# Sunflower_Schaltplan.net
KiCad netlist of a schematic drawn in EAGLE
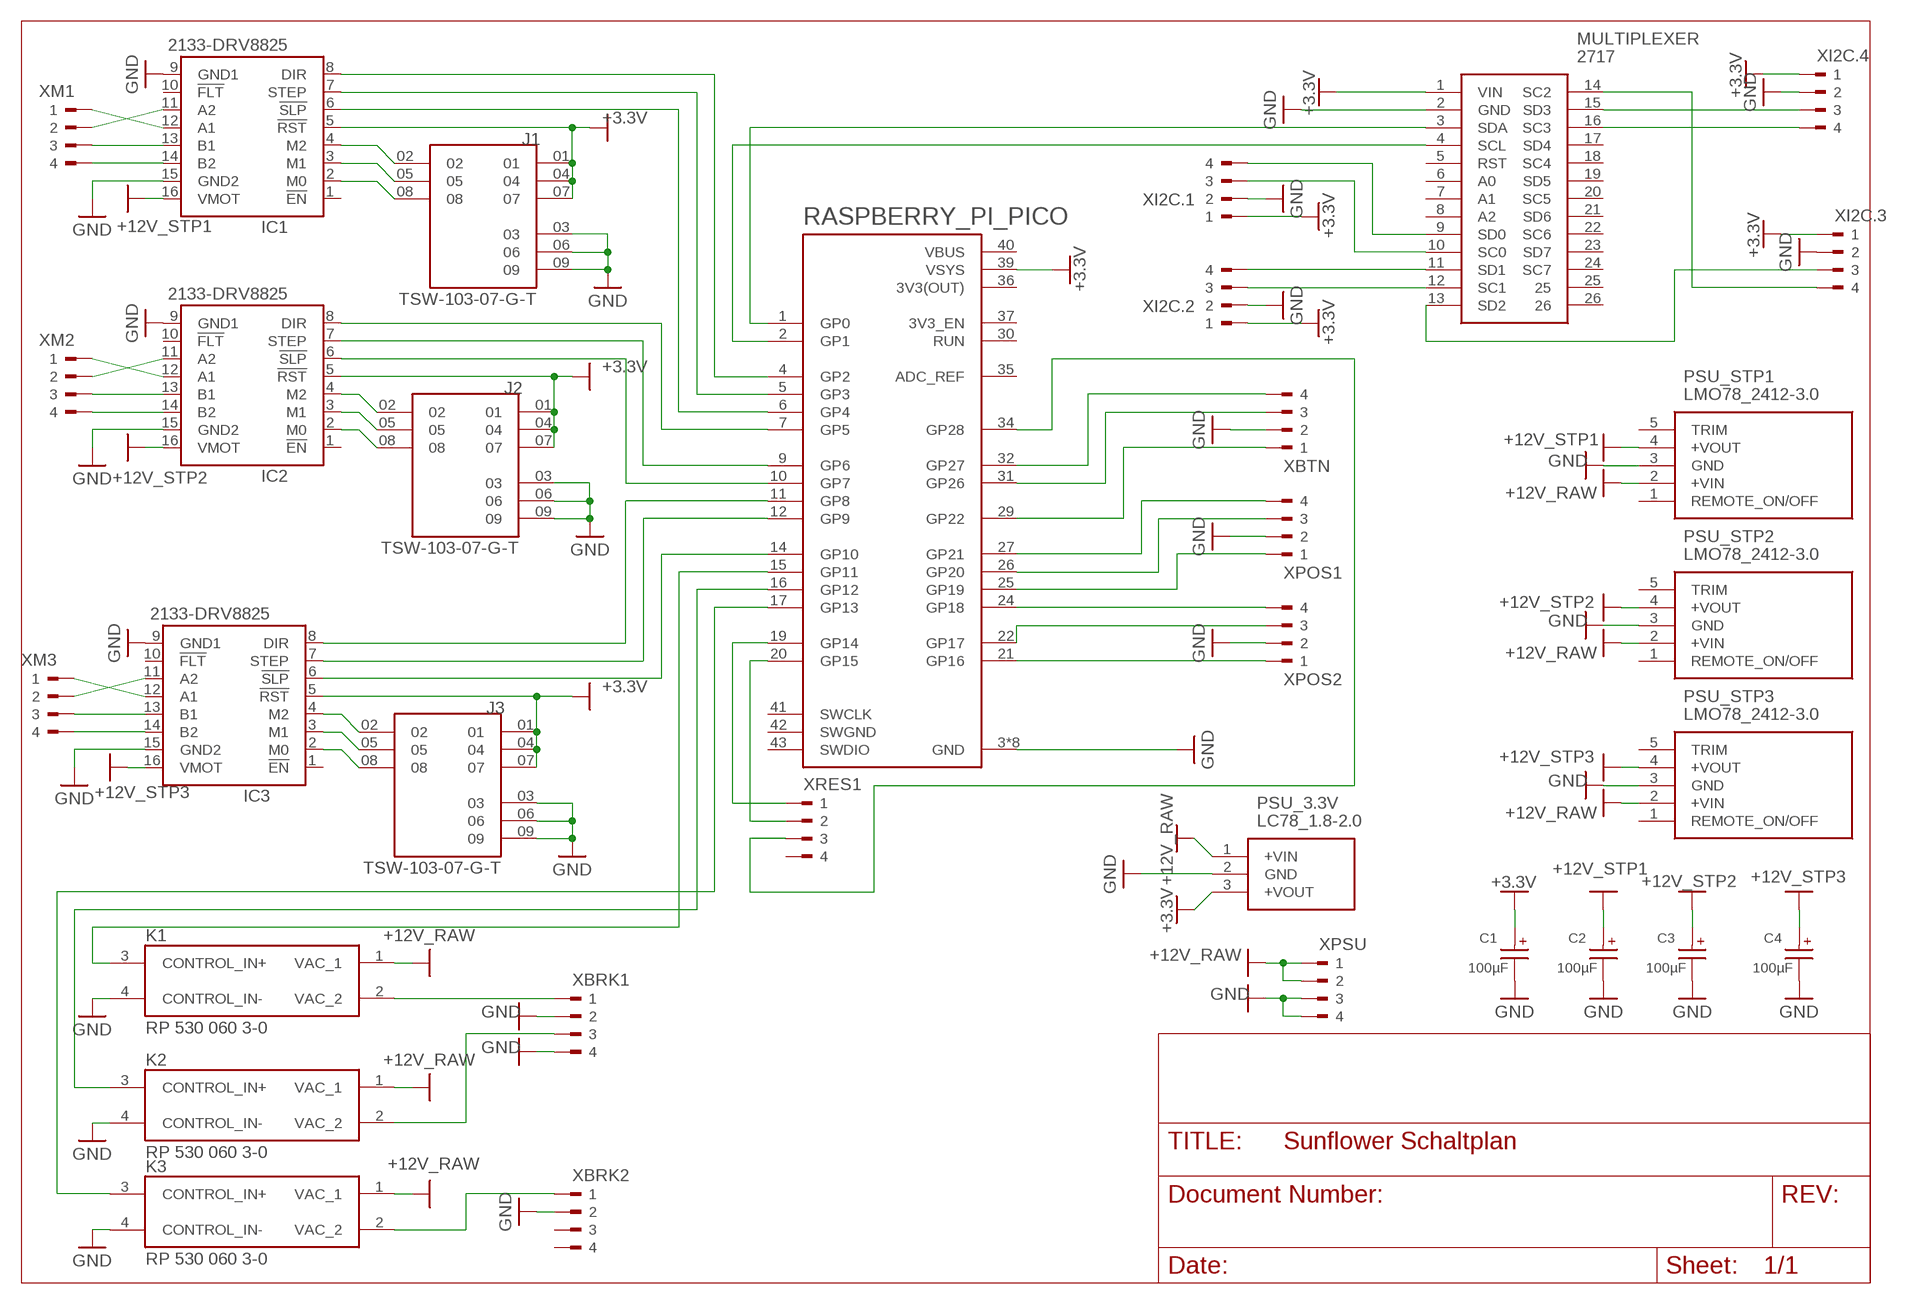
[diagram p0: schematic, sheet 1]

(export (version "E")
  (design (tool "Eeschema 10.0.6"))
  (components
    (comp (ref "C1")
      (value "100µF")
      (footprint "eagle-import:WCAP-ATET_10X16(DXL)")
      (libsource (lib "eagle-import") (part "WCAP-ATET_10X16_860130275006"))
    )
    (comp (ref "C2")
      (value "100µF")
      (footprint "eagle-import:WCAP-ATET_10X16(DXL)")
      (libsource (lib "eagle-import") (part "WCAP-ATET_10X16_860130275006"))
    )
    (comp (ref "C3")
      (value "100µF")
      (footprint "eagle-import:WCAP-ATET_10X16(DXL)")
      (libsource (lib "eagle-import") (part "WCAP-ATET_10X16_860130275006"))
    )
    (comp (ref "C4")
      (value "100µF")
      (footprint "eagle-import:WCAP-ATET_10X16(DXL)")
      (libsource (lib "eagle-import") (part "WCAP-ATET_10X16_860130275006"))
    )
    (comp (ref "IC1")
      (value "2133-DRV8825")
      (footprint "eagle-import:DRV8825")
      (libsource (lib "eagle-import") (part "2133-DRV8825"))
    )
    (comp (ref "IC2")
      (value "2133-DRV8825")
      (footprint "eagle-import:DRV8825")
      (libsource (lib "eagle-import") (part "2133-DRV8825"))
    )
    (comp (ref "IC3")
      (value "2133-DRV8825")
      (footprint "eagle-import:DRV8825")
      (libsource (lib "eagle-import") (part "2133-DRV8825"))
    )
    (comp (ref "J1")
      (value "TSW-103-07-G-T")
      (footprint "eagle-import:SAMTEC_TSW-103-07-G-T")
      (fields (field (name "MF") "Samtec Inc."))
      (libsource (lib "eagle-import") (part "TSW-103-07-G-T"))
    )
    (comp (ref "J2")
      (value "TSW-103-07-G-T")
      (footprint "eagle-import:SAMTEC_TSW-103-07-G-T")
      (fields (field (name "MF") "Samtec Inc."))
      (libsource (lib "eagle-import") (part "TSW-103-07-G-T"))
    )
    (comp (ref "J3")
      (value "TSW-103-07-G-T")
      (footprint "eagle-import:SAMTEC_TSW-103-07-G-T")
      (fields (field (name "MF") "Samtec Inc."))
      (libsource (lib "eagle-import") (part "TSW-103-07-G-T"))
    )
    (comp (ref "K1")
      (value "RP 530 060 3-0")
      (footprint "eagle-import:RELAY_RP1A23D5")
      (fields (field (name "MF") "Carlo Gavazzi Inc.") (field (name "MP") "RP1A23D5"))
      (libsource (lib "eagle-import") (part "RP1A23D5"))
    )
    (comp (ref "K2")
      (value "RP 530 060 3-0")
      (footprint "eagle-import:RELAY_RP1A23D5")
      (fields (field (name "MF") "Carlo Gavazzi Inc.") (field (name "MP") "RP1A23D5"))
      (libsource (lib "eagle-import") (part "RP1A23D5"))
    )
    (comp (ref "K3")
      (value "RP 530 060 3-0")
      (footprint "eagle-import:RELAY_RP1A23D5")
      (fields (field (name "MF") "Carlo Gavazzi Inc.") (field (name "MP") "RP1A23D5"))
      (libsource (lib "eagle-import") (part "RP1A23D5"))
    )
    (comp (ref "MULTIPLEXER")
      (value "2717")
      (footprint "eagle-import:2717")
      (fields (field (name "MOUSER_PART_NUMBER") "485-2717"))
      (libsource (lib "eagle-import") (part "2717"))
    )
    (comp (ref "PSU_3.3V")
      (value "LC78_1.8-2.0")
      (footprint "eagle-import:LC78_1820")
      (fields (field (name "MANUFACTURER_PART_NUMBER") "LC78_03-2.0"))
      (libsource (lib "eagle-import") (part "LC78_1.8-2.0"))
    )
    (comp (ref "PSU_STP1")
      (value "LMO78_2412-3.0")
      (footprint "eagle-import:LMO78_241230")
      (libsource (lib "eagle-import") (part "LMO78_2412-3.0"))
    )
    (comp (ref "PSU_STP2")
      (value "LMO78_2412-3.0")
      (footprint "eagle-import:LMO78_241230")
      (libsource (lib "eagle-import") (part "LMO78_2412-3.0"))
    )
    (comp (ref "PSU_STP3")
      (value "LMO78_2412-3.0")
      (footprint "eagle-import:LMO78_241230")
      (libsource (lib "eagle-import") (part "LMO78_2412-3.0"))
    )
    (comp (ref "RASPBERRY_PI_PICO")
      (value "RASPBERRY_PICOTH")
      (footprint "eagle-import:PICO-PKG-TH")
      (libsource (lib "eagle-import") (part "RASPBERRY_PICOTH"))
    )
    (comp (ref "XBRK1")
      (value "ANLOX_PT09304HBBN")
      (footprint "eagle-import:ANLOX_PT09304HBBN")
      (libsource (lib "eagle-import") (part "ANLOX_PT09304HBBN"))
    )
    (comp (ref "XBRK2")
      (value "ANLOX_PT09304HBBN")
      (footprint "eagle-import:ANLOX_PT09304HBBN")
      (libsource (lib "eagle-import") (part "ANLOX_PT09304HBBN"))
    )
    (comp (ref "XBTN")
      (value "ANLOX_PT09304HBBN")
      (footprint "eagle-import:ANLOX_PT09304HBBN")
      (libsource (lib "eagle-import") (part "ANLOX_PT09304HBBN"))
    )
    (comp (ref "XI2C.1")
      (value "ANLOX_PT09304HBBN")
      (footprint "eagle-import:ANLOX_PT09304HBBN")
      (libsource (lib "eagle-import") (part "ANLOX_PT09304HBBN"))
    )
    (comp (ref "XI2C.2")
      (value "ANLOX_PT09304HBBN")
      (footprint "eagle-import:ANLOX_PT09304HBBN")
      (libsource (lib "eagle-import") (part "ANLOX_PT09304HBBN"))
    )
    (comp (ref "XI2C.3")
      (value "ANLOX_PT09304HBBN")
      (footprint "eagle-import:ANLOX_PT09304HBBN")
      (libsource (lib "eagle-import") (part "ANLOX_PT09304HBBN"))
    )
    (comp (ref "XI2C.4")
      (value "ANLOX_PT09304HBBN")
      (footprint "eagle-import:ANLOX_PT09304HBBN")
      (libsource (lib "eagle-import") (part "ANLOX_PT09304HBBN"))
    )
    (comp (ref "XM1")
      (value "ANLOX_PT09304HBBN")
      (footprint "eagle-import:ANLOX_PT09304HBBN")
      (libsource (lib "eagle-import") (part "ANLOX_PT09304HBBN"))
    )
    (comp (ref "XM2")
      (value "ANLOX_PT09304HBBN")
      (footprint "eagle-import:ANLOX_PT09304HBBN")
      (libsource (lib "eagle-import") (part "ANLOX_PT09304HBBN"))
    )
    (comp (ref "XM3")
      (value "ANLOX_PT09304HBBN")
      (footprint "eagle-import:ANLOX_PT09304HBBN")
      (libsource (lib "eagle-import") (part "ANLOX_PT09304HBBN"))
    )
    (comp (ref "XPOS1")
      (value "ANLOX_PT09304HBBN")
      (footprint "eagle-import:ANLOX_PT09304HBBN")
      (libsource (lib "eagle-import") (part "ANLOX_PT09304HBBN"))
    )
    (comp (ref "XPOS2")
      (value "ANLOX_PT09304HBBN")
      (footprint "eagle-import:ANLOX_PT09304HBBN")
      (libsource (lib "eagle-import") (part "ANLOX_PT09304HBBN"))
    )
    (comp (ref "XPSU")
      (value "ANLOX_PT09304HBBN")
      (footprint "eagle-import:ANLOX_PT09304HBBN")
      (libsource (lib "eagle-import") (part "ANLOX_PT09304HBBN"))
    )
    (comp (ref "XRES1")
      (value "ANLOX_PT09304HBBN")
      (footprint "eagle-import:ANLOX_PT09304HBBN")
      (libsource (lib "eagle-import") (part "ANLOX_PT09304HBBN"))
    )
  )
  (nets
    (net (code "1") (name "+3.3V") (class "Default")
      (node (ref "C1") (pin "1") (pinfunction "+_1") (pintype "passive"))
      (node (ref "IC1") (pin "5") (pinfunction "~{RST}_5") (pintype "input"))
      (node (ref "IC2") (pin "5") (pinfunction "~{RST}_5") (pintype "input"))
      (node (ref "IC3") (pin "5") (pinfunction "~{RST}_5") (pintype "input"))
      (node (ref "J1") (pin "01") (pinfunction "01_01") (pintype "passive"))
      (node (ref "J1") (pin "04") (pinfunction "04_04") (pintype "passive"))
      (node (ref "J1") (pin "07") (pinfunction "07_07") (pintype "passive"))
      (node (ref "J2") (pin "01") (pinfunction "01_01") (pintype "passive"))
      (node (ref "J2") (pin "04") (pinfunction "04_04") (pintype "passive"))
      (node (ref "J2") (pin "07") (pinfunction "07_07") (pintype "passive"))
      (node (ref "J3") (pin "01") (pinfunction "01_01") (pintype "passive"))
      (node (ref "J3") (pin "04") (pinfunction "04_04") (pintype "passive"))
      (node (ref "J3") (pin "07") (pinfunction "07_07") (pintype "passive"))
      (node (ref "MULTIPLEXER") (pin "1") (pinfunction "VIN_1") (pintype "bidirectional"))
      (node (ref "PSU_3.3V") (pin "3") (pinfunction "+VOUT_3") (pintype "bidirectional"))
      (node (ref "RASPBERRY_PI_PICO") (pin "39") (pinfunction "VSYS_39") (pintype "power_in"))
      (node (ref "XI2C.1") (pin "1") (pinfunction "1_1") (pintype "passive"))
      (node (ref "XI2C.2") (pin "1") (pinfunction "1_1") (pintype "passive"))
      (node (ref "XI2C.3") (pin "1") (pinfunction "1_1") (pintype "passive"))
      (node (ref "XI2C.4") (pin "1") (pinfunction "1_1") (pintype "passive"))
    )
    (net (code "2") (name "+12V_RAW") (class "Default")
      (node (ref "K1") (pin "1") (pinfunction "VAC_1_1") (pintype "output"))
      (node (ref "K2") (pin "1") (pinfunction "VAC_1_1") (pintype "output"))
      (node (ref "K3") (pin "1") (pinfunction "VAC_1_1") (pintype "output"))
      (node (ref "PSU_3.3V") (pin "1") (pinfunction "+VIN_1") (pintype "bidirectional"))
      (node (ref "PSU_STP1") (pin "2") (pinfunction "+VIN_2") (pintype "bidirectional"))
      (node (ref "PSU_STP2") (pin "2") (pinfunction "+VIN_2") (pintype "bidirectional"))
      (node (ref "PSU_STP3") (pin "2") (pinfunction "+VIN_2") (pintype "bidirectional"))
      (node (ref "XPSU") (pin "1") (pinfunction "1_1") (pintype "passive"))
      (node (ref "XPSU") (pin "2") (pinfunction "2_2") (pintype "passive"))
    )
    (net (code "3") (name "+12V_STP1") (class "Default")
      (node (ref "C2") (pin "1") (pinfunction "+_1") (pintype "passive"))
      (node (ref "IC1") (pin "16") (pinfunction "VMOT_16") (pintype "power_in"))
      (node (ref "PSU_STP1") (pin "4") (pinfunction "+VOUT_4") (pintype "bidirectional"))
    )
    (net (code "4") (name "+12V_STP2") (class "Default")
      (node (ref "C3") (pin "1") (pinfunction "+_1") (pintype "passive"))
      (node (ref "IC2") (pin "16") (pinfunction "VMOT_16") (pintype "power_in"))
      (node (ref "PSU_STP2") (pin "4") (pinfunction "+VOUT_4") (pintype "bidirectional"))
    )
    (net (code "5") (name "+12V_STP3") (class "Default")
      (node (ref "C4") (pin "1") (pinfunction "+_1") (pintype "passive"))
      (node (ref "IC3") (pin "16") (pinfunction "VMOT_16") (pintype "power_in"))
      (node (ref "PSU_STP3") (pin "4") (pinfunction "+VOUT_4") (pintype "bidirectional"))
    )
    (net (code "6") (name "/3V3(OUT)") (class "Default")
      (node (ref "RASPBERRY_PI_PICO") (pin "36") (pinfunction "3V3(OUT)_36") (pintype "power_in"))
    )
    (net (code "7") (name "/SWGND") (class "Default")
      (node (ref "RASPBERRY_PI_PICO") (pin "42") (pinfunction "SWGND_42") (pintype "power_in"))
    )
    (net (code "8") (name "/VBUS") (class "Default")
      (node (ref "RASPBERRY_PI_PICO") (pin "40") (pinfunction "VBUS_40") (pintype "power_in"))
    )
    (net (code "9") (name "GND") (class "Default")
      (node (ref "C1") (pin "2") (pinfunction "-_2") (pintype "passive"))
      (node (ref "C2") (pin "2") (pinfunction "-_2") (pintype "passive"))
      (node (ref "C3") (pin "2") (pinfunction "-_2") (pintype "passive"))
      (node (ref "C4") (pin "2") (pinfunction "-_2") (pintype "passive"))
      (node (ref "IC1") (pin "15") (pinfunction "GND2_15") (pintype "power_in"))
      (node (ref "IC1") (pin "9") (pinfunction "GND1_9") (pintype "power_in"))
      (node (ref "IC2") (pin "15") (pinfunction "GND2_15") (pintype "power_in"))
      (node (ref "IC2") (pin "9") (pinfunction "GND1_9") (pintype "power_in"))
      (node (ref "IC3") (pin "15") (pinfunction "GND2_15") (pintype "power_in"))
      (node (ref "IC3") (pin "9") (pinfunction "GND1_9") (pintype "power_in"))
      (node (ref "J1") (pin "03") (pinfunction "03_03") (pintype "passive"))
      (node (ref "J1") (pin "06") (pinfunction "06_06") (pintype "passive"))
      (node (ref "J1") (pin "09") (pinfunction "09_09") (pintype "passive"))
      (node (ref "J2") (pin "03") (pinfunction "03_03") (pintype "passive"))
      (node (ref "J2") (pin "06") (pinfunction "06_06") (pintype "passive"))
      (node (ref "J2") (pin "09") (pinfunction "09_09") (pintype "passive"))
      (node (ref "J3") (pin "03") (pinfunction "03_03") (pintype "passive"))
      (node (ref "J3") (pin "06") (pinfunction "06_06") (pintype "passive"))
      (node (ref "J3") (pin "09") (pinfunction "09_09") (pintype "passive"))
      (node (ref "K1") (pin "4") (pinfunction "CONTROL_IN-_4") (pintype "input"))
      (node (ref "K2") (pin "4") (pinfunction "CONTROL_IN-_4") (pintype "input"))
      (node (ref "K3") (pin "4") (pinfunction "CONTROL_IN-_4") (pintype "input"))
      (node (ref "MULTIPLEXER") (pin "2") (pinfunction "GND_2") (pintype "bidirectional"))
      (node (ref "PSU_3.3V") (pin "2") (pinfunction "GND_2") (pintype "bidirectional"))
      (node (ref "PSU_STP1") (pin "3") (pinfunction "GND_3") (pintype "bidirectional"))
      (node (ref "PSU_STP2") (pin "3") (pinfunction "GND_3") (pintype "bidirectional"))
      (node (ref "PSU_STP3") (pin "3") (pinfunction "GND_3") (pintype "bidirectional"))
      (node (ref "RASPBERRY_PI_PICO") (pin "13") (pinfunction "GND_13") (pintype "power_in"))
      (node (ref "RASPBERRY_PI_PICO") (pin "18") (pinfunction "GND_18") (pintype "power_in"))
      (node (ref "RASPBERRY_PI_PICO") (pin "23") (pinfunction "GND_23") (pintype "power_in"))
      (node (ref "RASPBERRY_PI_PICO") (pin "28") (pinfunction "GND_28") (pintype "power_in"))
      (node (ref "RASPBERRY_PI_PICO") (pin "3") (pinfunction "GND_3") (pintype "power_in"))
      (node (ref "RASPBERRY_PI_PICO") (pin "33") (pinfunction "GND_33") (pintype "power_in"))
      (node (ref "RASPBERRY_PI_PICO") (pin "38") (pinfunction "GND_38") (pintype "power_in"))
      (node (ref "RASPBERRY_PI_PICO") (pin "8") (pinfunction "GND_8") (pintype "power_in"))
      (node (ref "XBRK1") (pin "2") (pinfunction "2_2") (pintype "passive"))
      (node (ref "XBRK1") (pin "4") (pinfunction "4_4") (pintype "passive"))
      (node (ref "XBRK2") (pin "2") (pinfunction "2_2") (pintype "passive"))
      (node (ref "XBTN") (pin "2") (pinfunction "2_2") (pintype "passive"))
      (node (ref "XI2C.1") (pin "2") (pinfunction "2_2") (pintype "passive"))
      (node (ref "XI2C.2") (pin "2") (pinfunction "2_2") (pintype "passive"))
      (node (ref "XI2C.3") (pin "2") (pinfunction "2_2") (pintype "passive"))
      (node (ref "XI2C.4") (pin "2") (pinfunction "2_2") (pintype "passive"))
      (node (ref "XPOS1") (pin "2") (pinfunction "2_2") (pintype "passive"))
      (node (ref "XPOS2") (pin "2") (pinfunction "2_2") (pintype "passive"))
      (node (ref "XPSU") (pin "3") (pinfunction "3_3") (pintype "passive"))
      (node (ref "XPSU") (pin "4") (pinfunction "4_4") (pintype "passive"))
    )
    (net (code "10") (name "Net-(IC1-A1)") (class "Default")
      (node (ref "IC1") (pin "12") (pinfunction "A1_12") (pintype "output"))
      (node (ref "XM1") (pin "1") (pinfunction "1_1") (pintype "passive"))
    )
    (net (code "11") (name "Net-(IC1-A2)") (class "Default")
      (node (ref "IC1") (pin "11") (pinfunction "A2_11") (pintype "output"))
      (node (ref "XM1") (pin "2") (pinfunction "2_2") (pintype "passive"))
    )
    (net (code "12") (name "Net-(IC1-B1)") (class "Default")
      (node (ref "IC1") (pin "13") (pinfunction "B1_13") (pintype "output"))
      (node (ref "XM1") (pin "3") (pinfunction "3_3") (pintype "passive"))
    )
    (net (code "13") (name "Net-(IC1-B2)") (class "Default")
      (node (ref "IC1") (pin "14") (pinfunction "B2_14") (pintype "output"))
      (node (ref "XM1") (pin "4") (pinfunction "4_4") (pintype "passive"))
    )
    (net (code "14") (name "Net-(IC1-DIR)") (class "Default")
      (node (ref "IC1") (pin "8") (pinfunction "DIR_8") (pintype "input"))
      (node (ref "RASPBERRY_PI_PICO") (pin "4") (pinfunction "GP2_4") (pintype "bidirectional"))
    )
    (net (code "15") (name "Net-(IC1-M0)") (class "Default")
      (node (ref "IC1") (pin "2") (pinfunction "M0_2") (pintype "passive"))
      (node (ref "J1") (pin "08") (pinfunction "08_08") (pintype "passive"))
    )
    (net (code "16") (name "Net-(IC1-M1)") (class "Default")
      (node (ref "IC1") (pin "3") (pinfunction "M1_3") (pintype "passive"))
      (node (ref "J1") (pin "05") (pinfunction "05_05") (pintype "passive"))
    )
    (net (code "17") (name "Net-(IC1-M2)") (class "Default")
      (node (ref "IC1") (pin "4") (pinfunction "M2_4") (pintype "passive"))
      (node (ref "J1") (pin "02") (pinfunction "02_02") (pintype "passive"))
    )
    (net (code "18") (name "Net-(IC1-STEP)") (class "Default")
      (node (ref "IC1") (pin "7") (pinfunction "STEP_7") (pintype "input"))
      (node (ref "RASPBERRY_PI_PICO") (pin "5") (pinfunction "GP3_5") (pintype "bidirectional"))
    )
    (net (code "19") (name "Net-(IC1-~{SLP})") (class "Default")
      (node (ref "IC1") (pin "6") (pinfunction "~{SLP}_6") (pintype "input"))
      (node (ref "RASPBERRY_PI_PICO") (pin "6") (pinfunction "GP4_6") (pintype "bidirectional"))
    )
    (net (code "20") (name "Net-(IC2-A1)") (class "Default")
      (node (ref "IC2") (pin "12") (pinfunction "A1_12") (pintype "output"))
      (node (ref "XM2") (pin "1") (pinfunction "1_1") (pintype "passive"))
    )
    (net (code "21") (name "Net-(IC2-A2)") (class "Default")
      (node (ref "IC2") (pin "11") (pinfunction "A2_11") (pintype "output"))
      (node (ref "XM2") (pin "2") (pinfunction "2_2") (pintype "passive"))
    )
    (net (code "22") (name "Net-(IC2-B1)") (class "Default")
      (node (ref "IC2") (pin "13") (pinfunction "B1_13") (pintype "output"))
      (node (ref "XM2") (pin "3") (pinfunction "3_3") (pintype "passive"))
    )
    (net (code "23") (name "Net-(IC2-B2)") (class "Default")
      (node (ref "IC2") (pin "14") (pinfunction "B2_14") (pintype "output"))
      (node (ref "XM2") (pin "4") (pinfunction "4_4") (pintype "passive"))
    )
    (net (code "24") (name "Net-(IC2-DIR)") (class "Default")
      (node (ref "IC2") (pin "8") (pinfunction "DIR_8") (pintype "input"))
      (node (ref "RASPBERRY_PI_PICO") (pin "7") (pinfunction "GP5_7") (pintype "bidirectional"))
    )
    (net (code "25") (name "Net-(IC2-M0)") (class "Default")
      (node (ref "IC2") (pin "2") (pinfunction "M0_2") (pintype "passive"))
      (node (ref "J2") (pin "08") (pinfunction "08_08") (pintype "passive"))
    )
    (net (code "26") (name "Net-(IC2-M1)") (class "Default")
      (node (ref "IC2") (pin "3") (pinfunction "M1_3") (pintype "passive"))
      (node (ref "J2") (pin "05") (pinfunction "05_05") (pintype "passive"))
    )
    (net (code "27") (name "Net-(IC2-M2)") (class "Default")
      (node (ref "IC2") (pin "4") (pinfunction "M2_4") (pintype "passive"))
      (node (ref "J2") (pin "02") (pinfunction "02_02") (pintype "passive"))
    )
    (net (code "28") (name "Net-(IC2-STEP)") (class "Default")
      (node (ref "IC2") (pin "7") (pinfunction "STEP_7") (pintype "input"))
      (node (ref "RASPBERRY_PI_PICO") (pin "9") (pinfunction "GP6_9") (pintype "bidirectional"))
    )
    (net (code "29") (name "Net-(IC2-~{SLP})") (class "Default")
      (node (ref "IC2") (pin "6") (pinfunction "~{SLP}_6") (pintype "input"))
      (node (ref "RASPBERRY_PI_PICO") (pin "10") (pinfunction "GP7_10") (pintype "bidirectional"))
    )
    (net (code "30") (name "Net-(IC3-A1)") (class "Default")
      (node (ref "IC3") (pin "12") (pinfunction "A1_12") (pintype "output"))
      (node (ref "XM3") (pin "1") (pinfunction "1_1") (pintype "passive"))
    )
    (net (code "31") (name "Net-(IC3-A2)") (class "Default")
      (node (ref "IC3") (pin "11") (pinfunction "A2_11") (pintype "output"))
      (node (ref "XM3") (pin "2") (pinfunction "2_2") (pintype "passive"))
    )
    (net (code "32") (name "Net-(IC3-B1)") (class "Default")
      (node (ref "IC3") (pin "13") (pinfunction "B1_13") (pintype "output"))
      (node (ref "XM3") (pin "3") (pinfunction "3_3") (pintype "passive"))
    )
    (net (code "33") (name "Net-(IC3-B2)") (class "Default")
      (node (ref "IC3") (pin "14") (pinfunction "B2_14") (pintype "output"))
      (node (ref "XM3") (pin "4") (pinfunction "4_4") (pintype "passive"))
    )
    (net (code "34") (name "Net-(IC3-DIR)") (class "Default")
      (node (ref "IC3") (pin "8") (pinfunction "DIR_8") (pintype "input"))
      (node (ref "RASPBERRY_PI_PICO") (pin "11") (pinfunction "GP8_11") (pintype "bidirectional"))
    )
    (net (code "35") (name "Net-(IC3-M0)") (class "Default")
      (node (ref "IC3") (pin "2") (pinfunction "M0_2") (pintype "passive"))
      (node (ref "J3") (pin "08") (pinfunction "08_08") (pintype "passive"))
    )
    (net (code "36") (name "Net-(IC3-M1)") (class "Default")
      (node (ref "IC3") (pin "3") (pinfunction "M1_3") (pintype "passive"))
      (node (ref "J3") (pin "05") (pinfunction "05_05") (pintype "passive"))
    )
    (net (code "37") (name "Net-(IC3-M2)") (class "Default")
      (node (ref "IC3") (pin "4") (pinfunction "M2_4") (pintype "passive"))
      (node (ref "J3") (pin "02") (pinfunction "02_02") (pintype "passive"))
    )
    (net (code "38") (name "Net-(IC3-STEP)") (class "Default")
      (node (ref "IC3") (pin "7") (pinfunction "STEP_7") (pintype "input"))
      (node (ref "RASPBERRY_PI_PICO") (pin "12") (pinfunction "GP9_12") (pintype "bidirectional"))
    )
    (net (code "39") (name "Net-(IC3-~{SLP})") (class "Default")
      (node (ref "IC3") (pin "6") (pinfunction "~{SLP}_6") (pintype "input"))
      (node (ref "RASPBERRY_PI_PICO") (pin "14") (pinfunction "GP10_14") (pintype "bidirectional"))
    )
    (net (code "40") (name "Net-(K1-CONTROL_IN+)") (class "Default")
      (node (ref "K1") (pin "3") (pinfunction "CONTROL_IN+_3") (pintype "input"))
      (node (ref "RASPBERRY_PI_PICO") (pin "15") (pinfunction "GP11_15") (pintype "bidirectional"))
    )
    (net (code "41") (name "Net-(K1-VAC_2)") (class "Default")
      (node (ref "K1") (pin "2") (pinfunction "VAC_2_2") (pintype "output"))
      (node (ref "XBRK1") (pin "1") (pinfunction "1_1") (pintype "passive"))
    )
    (net (code "42") (name "Net-(K2-CONTROL_IN+)") (class "Default")
      (node (ref "K2") (pin "3") (pinfunction "CONTROL_IN+_3") (pintype "input"))
      (node (ref "RASPBERRY_PI_PICO") (pin "16") (pinfunction "GP12_16") (pintype "bidirectional"))
    )
    (net (code "43") (name "Net-(K2-VAC_2)") (class "Default")
      (node (ref "K2") (pin "2") (pinfunction "VAC_2_2") (pintype "output"))
      (node (ref "XBRK1") (pin "3") (pinfunction "3_3") (pintype "passive"))
    )
    (net (code "44") (name "Net-(K3-CONTROL_IN+)") (class "Default")
      (node (ref "K3") (pin "3") (pinfunction "CONTROL_IN+_3") (pintype "input"))
      (node (ref "RASPBERRY_PI_PICO") (pin "17") (pinfunction "GP13_17") (pintype "bidirectional"))
    )
    (net (code "45") (name "Net-(K3-VAC_2)") (class "Default")
      (node (ref "K3") (pin "2") (pinfunction "VAC_2_2") (pintype "output"))
      (node (ref "XBRK2") (pin "1") (pinfunction "1_1") (pintype "passive"))
    )
    (net (code "46") (name "Net-(MULTIPLEXER-SC0)") (class "Default")
      (node (ref "MULTIPLEXER") (pin "10") (pinfunction "SC0_10") (pintype "bidirectional"))
      (node (ref "XI2C.1") (pin "3") (pinfunction "3_3") (pintype "passive"))
    )
    (net (code "47") (name "Net-(MULTIPLEXER-SC1)") (class "Default")
      (node (ref "MULTIPLEXER") (pin "12") (pinfunction "SC1_12") (pintype "bidirectional"))
      (node (ref "XI2C.2") (pin "3") (pinfunction "3_3") (pintype "passive"))
    )
    (net (code "48") (name "Net-(MULTIPLEXER-SC2)") (class "Default")
      (node (ref "MULTIPLEXER") (pin "14") (pinfunction "SC2_14") (pintype "bidirectional"))
      (node (ref "XI2C.3") (pin "4") (pinfunction "4_4") (pintype "passive"))
    )
    (net (code "49") (name "Net-(MULTIPLEXER-SC3)") (class "Default")
      (node (ref "MULTIPLEXER") (pin "16") (pinfunction "SC3_16") (pintype "bidirectional"))
      (node (ref "XI2C.4") (pin "4") (pinfunction "4_4") (pintype "passive"))
    )
    (net (code "50") (name "Net-(MULTIPLEXER-SCL)") (class "Default")
      (node (ref "MULTIPLEXER") (pin "4") (pinfunction "SCL_4") (pintype "bidirectional"))
      (node (ref "RASPBERRY_PI_PICO") (pin "2") (pinfunction "GP1_2") (pintype "bidirectional"))
    )
    (net (code "51") (name "Net-(MULTIPLEXER-SD0)") (class "Default")
      (node (ref "MULTIPLEXER") (pin "9") (pinfunction "SD0_9") (pintype "bidirectional"))
      (node (ref "XI2C.1") (pin "4") (pinfunction "4_4") (pintype "passive"))
    )
    (net (code "52") (name "Net-(MULTIPLEXER-SD1)") (class "Default")
      (node (ref "MULTIPLEXER") (pin "11") (pinfunction "SD1_11") (pintype "bidirectional"))
      (node (ref "XI2C.2") (pin "4") (pinfunction "4_4") (pintype "passive"))
    )
    (net (code "53") (name "Net-(MULTIPLEXER-SD2)") (class "Default")
      (node (ref "MULTIPLEXER") (pin "13") (pinfunction "SD2_13") (pintype "bidirectional"))
      (node (ref "XI2C.3") (pin "3") (pinfunction "3_3") (pintype "passive"))
    )
    (net (code "54") (name "Net-(MULTIPLEXER-SD3)") (class "Default")
      (node (ref "MULTIPLEXER") (pin "15") (pinfunction "SD3_15") (pintype "bidirectional"))
      (node (ref "XI2C.4") (pin "3") (pinfunction "3_3") (pintype "passive"))
    )
    (net (code "55") (name "Net-(MULTIPLEXER-SDA)") (class "Default")
      (node (ref "MULTIPLEXER") (pin "3") (pinfunction "SDA_3") (pintype "bidirectional"))
      (node (ref "RASPBERRY_PI_PICO") (pin "1") (pinfunction "GP0_1") (pintype "bidirectional"))
    )
    (net (code "56") (name "Net-(RASPBERRY_PI_PICO-GP14)") (class "Default")
      (node (ref "RASPBERRY_PI_PICO") (pin "19") (pinfunction "GP14_19") (pintype "bidirectional"))
      (node (ref "XRES1") (pin "1") (pinfunction "1_1") (pintype "passive"))
    )
    (net (code "57") (name "Net-(RASPBERRY_PI_PICO-GP15)") (class "Default")
      (node (ref "RASPBERRY_PI_PICO") (pin "20") (pinfunction "GP15_20") (pintype "bidirectional"))
      (node (ref "XRES1") (pin "2") (pinfunction "2_2") (pintype "passive"))
    )
    (net (code "58") (name "Net-(RASPBERRY_PI_PICO-GP16)") (class "Default")
      (node (ref "RASPBERRY_PI_PICO") (pin "21") (pinfunction "GP16_21") (pintype "bidirectional"))
      (node (ref "XPOS2") (pin "1") (pinfunction "1_1") (pintype "passive"))
    )
    (net (code "59") (name "Net-(RASPBERRY_PI_PICO-GP17)") (class "Default")
      (node (ref "RASPBERRY_PI_PICO") (pin "22") (pinfunction "GP17_22") (pintype "bidirectional"))
      (node (ref "XPOS2") (pin "3") (pinfunction "3_3") (pintype "passive"))
    )
    (net (code "60") (name "Net-(RASPBERRY_PI_PICO-GP18)") (class "Default")
      (node (ref "RASPBERRY_PI_PICO") (pin "24") (pinfunction "GP18_24") (pintype "bidirectional"))
      (node (ref "XPOS2") (pin "4") (pinfunction "4_4") (pintype "passive"))
    )
    (net (code "61") (name "Net-(RASPBERRY_PI_PICO-GP19)") (class "Default")
      (node (ref "RASPBERRY_PI_PICO") (pin "25") (pinfunction "GP19_25") (pintype "bidirectional"))
      (node (ref "XPOS1") (pin "1") (pinfunction "1_1") (pintype "passive"))
    )
    (net (code "62") (name "Net-(RASPBERRY_PI_PICO-GP20)") (class "Default")
      (node (ref "RASPBERRY_PI_PICO") (pin "26") (pinfunction "GP20_26") (pintype "bidirectional"))
      (node (ref "XPOS1") (pin "3") (pinfunction "3_3") (pintype "passive"))
    )
    (net (code "63") (name "Net-(RASPBERRY_PI_PICO-GP21)") (class "Default")
      (node (ref "RASPBERRY_PI_PICO") (pin "27") (pinfunction "GP21_27") (pintype "bidirectional"))
      (node (ref "XPOS1") (pin "4") (pinfunction "4_4") (pintype "passive"))
    )
    (net (code "64") (name "Net-(RASPBERRY_PI_PICO-GP22)") (class "Default")
      (node (ref "RASPBERRY_PI_PICO") (pin "29") (pinfunction "GP22_29") (pintype "bidirectional"))
      (node (ref "XBTN") (pin "1") (pinfunction "1_1") (pintype "passive"))
    )
    (net (code "65") (name "Net-(RASPBERRY_PI_PICO-GP26)") (class "Default")
      (node (ref "RASPBERRY_PI_PICO") (pin "31") (pinfunction "GP26_31") (pintype "bidirectional"))
      (node (ref "XBTN") (pin "3") (pinfunction "3_3") (pintype "passive"))
    )
    (net (code "66") (name "Net-(RASPBERRY_PI_PICO-GP27)") (class "Default")
      (node (ref "RASPBERRY_PI_PICO") (pin "32") (pinfunction "GP27_32") (pintype "bidirectional"))
      (node (ref "XBTN") (pin "4") (pinfunction "4_4") (pintype "passive"))
    )
    (net (code "67") (name "Net-(RASPBERRY_PI_PICO-GP28)") (class "Default")
      (node (ref "RASPBERRY_PI_PICO") (pin "34") (pinfunction "GP28_34") (pintype "bidirectional"))
      (node (ref "XRES1") (pin "3") (pinfunction "3_3") (pintype "passive"))
    )
    (net (code "68") (name "unconnected-(IC1-~{EN}-Pad1)") (class "Default")
      (node (ref "IC1") (pin "1") (pinfunction "~{EN}_1") (pintype "passive"))
    )
    (net (code "69") (name "unconnected-(IC1-~{FLT}-Pad10)") (class "Default")
      (node (ref "IC1") (pin "10") (pinfunction "~{FLT}_10") (pintype "open_collector"))
    )
    (net (code "70") (name "unconnected-(IC2-~{EN}-Pad1)") (class "Default")
      (node (ref "IC2") (pin "1") (pinfunction "~{EN}_1") (pintype "passive"))
    )
    (net (code "71") (name "unconnected-(IC2-~{FLT}-Pad10)") (class "Default")
      (node (ref "IC2") (pin "10") (pinfunction "~{FLT}_10") (pintype "open_collector"))
    )
    (net (code "72") (name "unconnected-(IC3-~{EN}-Pad1)") (class "Default")
      (node (ref "IC3") (pin "1") (pinfunction "~{EN}_1") (pintype "passive"))
    )
    (net (code "73") (name "unconnected-(IC3-~{FLT}-Pad10)") (class "Default")
      (node (ref "IC3") (pin "10") (pinfunction "~{FLT}_10") (pintype "open_collector"))
    )
    (net (code "74") (name "unconnected-(MULTIPLEXER-A0-Pad6)") (class "Default")
      (node (ref "MULTIPLEXER") (pin "6") (pinfunction "A0_6") (pintype "bidirectional"))
    )
    (net (code "75") (name "unconnected-(MULTIPLEXER-A1-Pad7)") (class "Default")
      (node (ref "MULTIPLEXER") (pin "7") (pinfunction "A1_7") (pintype "bidirectional"))
    )
    (net (code "76") (name "unconnected-(MULTIPLEXER-A2-Pad8)") (class "Default")
      (node (ref "MULTIPLEXER") (pin "8") (pinfunction "A2_8") (pintype "bidirectional"))
    )
    (net (code "77") (name "unconnected-(MULTIPLEXER-Pad25)") (class "Default")
      (node (ref "MULTIPLEXER") (pin "25") (pinfunction "25_25") (pintype "bidirectional"))
    )
    (net (code "78") (name "unconnected-(MULTIPLEXER-Pad26)") (class "Default")
      (node (ref "MULTIPLEXER") (pin "26") (pinfunction "26_26") (pintype "bidirectional"))
    )
    (net (code "79") (name "unconnected-(MULTIPLEXER-RST-Pad5)") (class "Default")
      (node (ref "MULTIPLEXER") (pin "5") (pinfunction "RST_5") (pintype "bidirectional"))
    )
    (net (code "80") (name "unconnected-(MULTIPLEXER-SC4-Pad18)") (class "Default")
      (node (ref "MULTIPLEXER") (pin "18") (pinfunction "SC4_18") (pintype "bidirectional"))
    )
    (net (code "81") (name "unconnected-(MULTIPLEXER-SC5-Pad20)") (class "Default")
      (node (ref "MULTIPLEXER") (pin "20") (pinfunction "SC5_20") (pintype "bidirectional"))
    )
    (net (code "82") (name "unconnected-(MULTIPLEXER-SC6-Pad22)") (class "Default")
      (node (ref "MULTIPLEXER") (pin "22") (pinfunction "SC6_22") (pintype "bidirectional"))
    )
    (net (code "83") (name "unconnected-(MULTIPLEXER-SC7-Pad24)") (class "Default")
      (node (ref "MULTIPLEXER") (pin "24") (pinfunction "SC7_24") (pintype "bidirectional"))
    )
    (net (code "84") (name "unconnected-(MULTIPLEXER-SD4-Pad17)") (class "Default")
      (node (ref "MULTIPLEXER") (pin "17") (pinfunction "SD4_17") (pintype "bidirectional"))
    )
    (net (code "85") (name "unconnected-(MULTIPLEXER-SD5-Pad19)") (class "Default")
      (node (ref "MULTIPLEXER") (pin "19") (pinfunction "SD5_19") (pintype "bidirectional"))
    )
    (net (code "86") (name "unconnected-(MULTIPLEXER-SD6-Pad21)") (class "Default")
      (node (ref "MULTIPLEXER") (pin "21") (pinfunction "SD6_21") (pintype "bidirectional"))
    )
    (net (code "87") (name "unconnected-(MULTIPLEXER-SD7-Pad23)") (class "Default")
      (node (ref "MULTIPLEXER") (pin "23") (pinfunction "SD7_23") (pintype "bidirectional"))
    )
    (net (code "88") (name "unconnected-(PSU_STP1-REMOTE_ON{slash}OFF-Pad1)") (class "Default")
      (node (ref "PSU_STP1") (pin "1") (pinfunction "REMOTE_ON/OFF_1") (pintype "bidirectional"))
    )
    (net (code "89") (name "unconnected-(PSU_STP1-TRIM-Pad5)") (class "Default")
      (node (ref "PSU_STP1") (pin "5") (pinfunction "TRIM_5") (pintype "bidirectional"))
    )
    (net (code "90") (name "unconnected-(PSU_STP2-REMOTE_ON{slash}OFF-Pad1)") (class "Default")
      (node (ref "PSU_STP2") (pin "1") (pinfunction "REMOTE_ON/OFF_1") (pintype "bidirectional"))
    )
    (net (code "91") (name "unconnected-(PSU_STP2-TRIM-Pad5)") (class "Default")
      (node (ref "PSU_STP2") (pin "5") (pinfunction "TRIM_5") (pintype "bidirectional"))
    )
    (net (code "92") (name "unconnected-(PSU_STP3-REMOTE_ON{slash}OFF-Pad1)") (class "Default")
      (node (ref "PSU_STP3") (pin "1") (pinfunction "REMOTE_ON/OFF_1") (pintype "bidirectional"))
    )
    (net (code "93") (name "unconnected-(PSU_STP3-TRIM-Pad5)") (class "Default")
      (node (ref "PSU_STP3") (pin "5") (pinfunction "TRIM_5") (pintype "bidirectional"))
    )
    (net (code "94") (name "unconnected-(RASPBERRY_PI_PICO-3V3_EN-Pad37)") (class "Default")
      (node (ref "RASPBERRY_PI_PICO") (pin "37") (pinfunction "3V3_EN_37") (pintype "input"))
    )
    (net (code "95") (name "unconnected-(RASPBERRY_PI_PICO-ADC_REF-Pad35)") (class "Default")
      (node (ref "RASPBERRY_PI_PICO") (pin "35") (pinfunction "ADC_REF_35") (pintype "input"))
    )
    (net (code "96") (name "unconnected-(RASPBERRY_PI_PICO-RUN-Pad30)") (class "Default")
      (node (ref "RASPBERRY_PI_PICO") (pin "30") (pinfunction "RUN_30") (pintype "input"))
    )
    (net (code "97") (name "unconnected-(RASPBERRY_PI_PICO-SWCLK-Pad41)") (class "Default")
      (node (ref "RASPBERRY_PI_PICO") (pin "41") (pinfunction "SWCLK_41") (pintype "input"))
    )
    (net (code "98") (name "unconnected-(RASPBERRY_PI_PICO-SWDIO-Pad43)") (class "Default")
      (node (ref "RASPBERRY_PI_PICO") (pin "43") (pinfunction "SWDIO_43") (pintype "bidirectional"))
    )
    (net (code "99") (name "unconnected-(XBRK2-Pad3)") (class "Default")
      (node (ref "XBRK2") (pin "3") (pinfunction "3_3") (pintype "passive"))
    )
    (net (code "100") (name "unconnected-(XBRK2-Pad4)") (class "Default")
      (node (ref "XBRK2") (pin "4") (pinfunction "4_4") (pintype "passive"))
    )
    (net (code "101") (name "unconnected-(XRES1-Pad4)") (class "Default")
      (node (ref "XRES1") (pin "4") (pinfunction "4_4") (pintype "passive"))
    )
  )
)
